# 7CUN_RGB_V0_0_1.net
KiCad netlist of a schematic drawn in Altium Designer
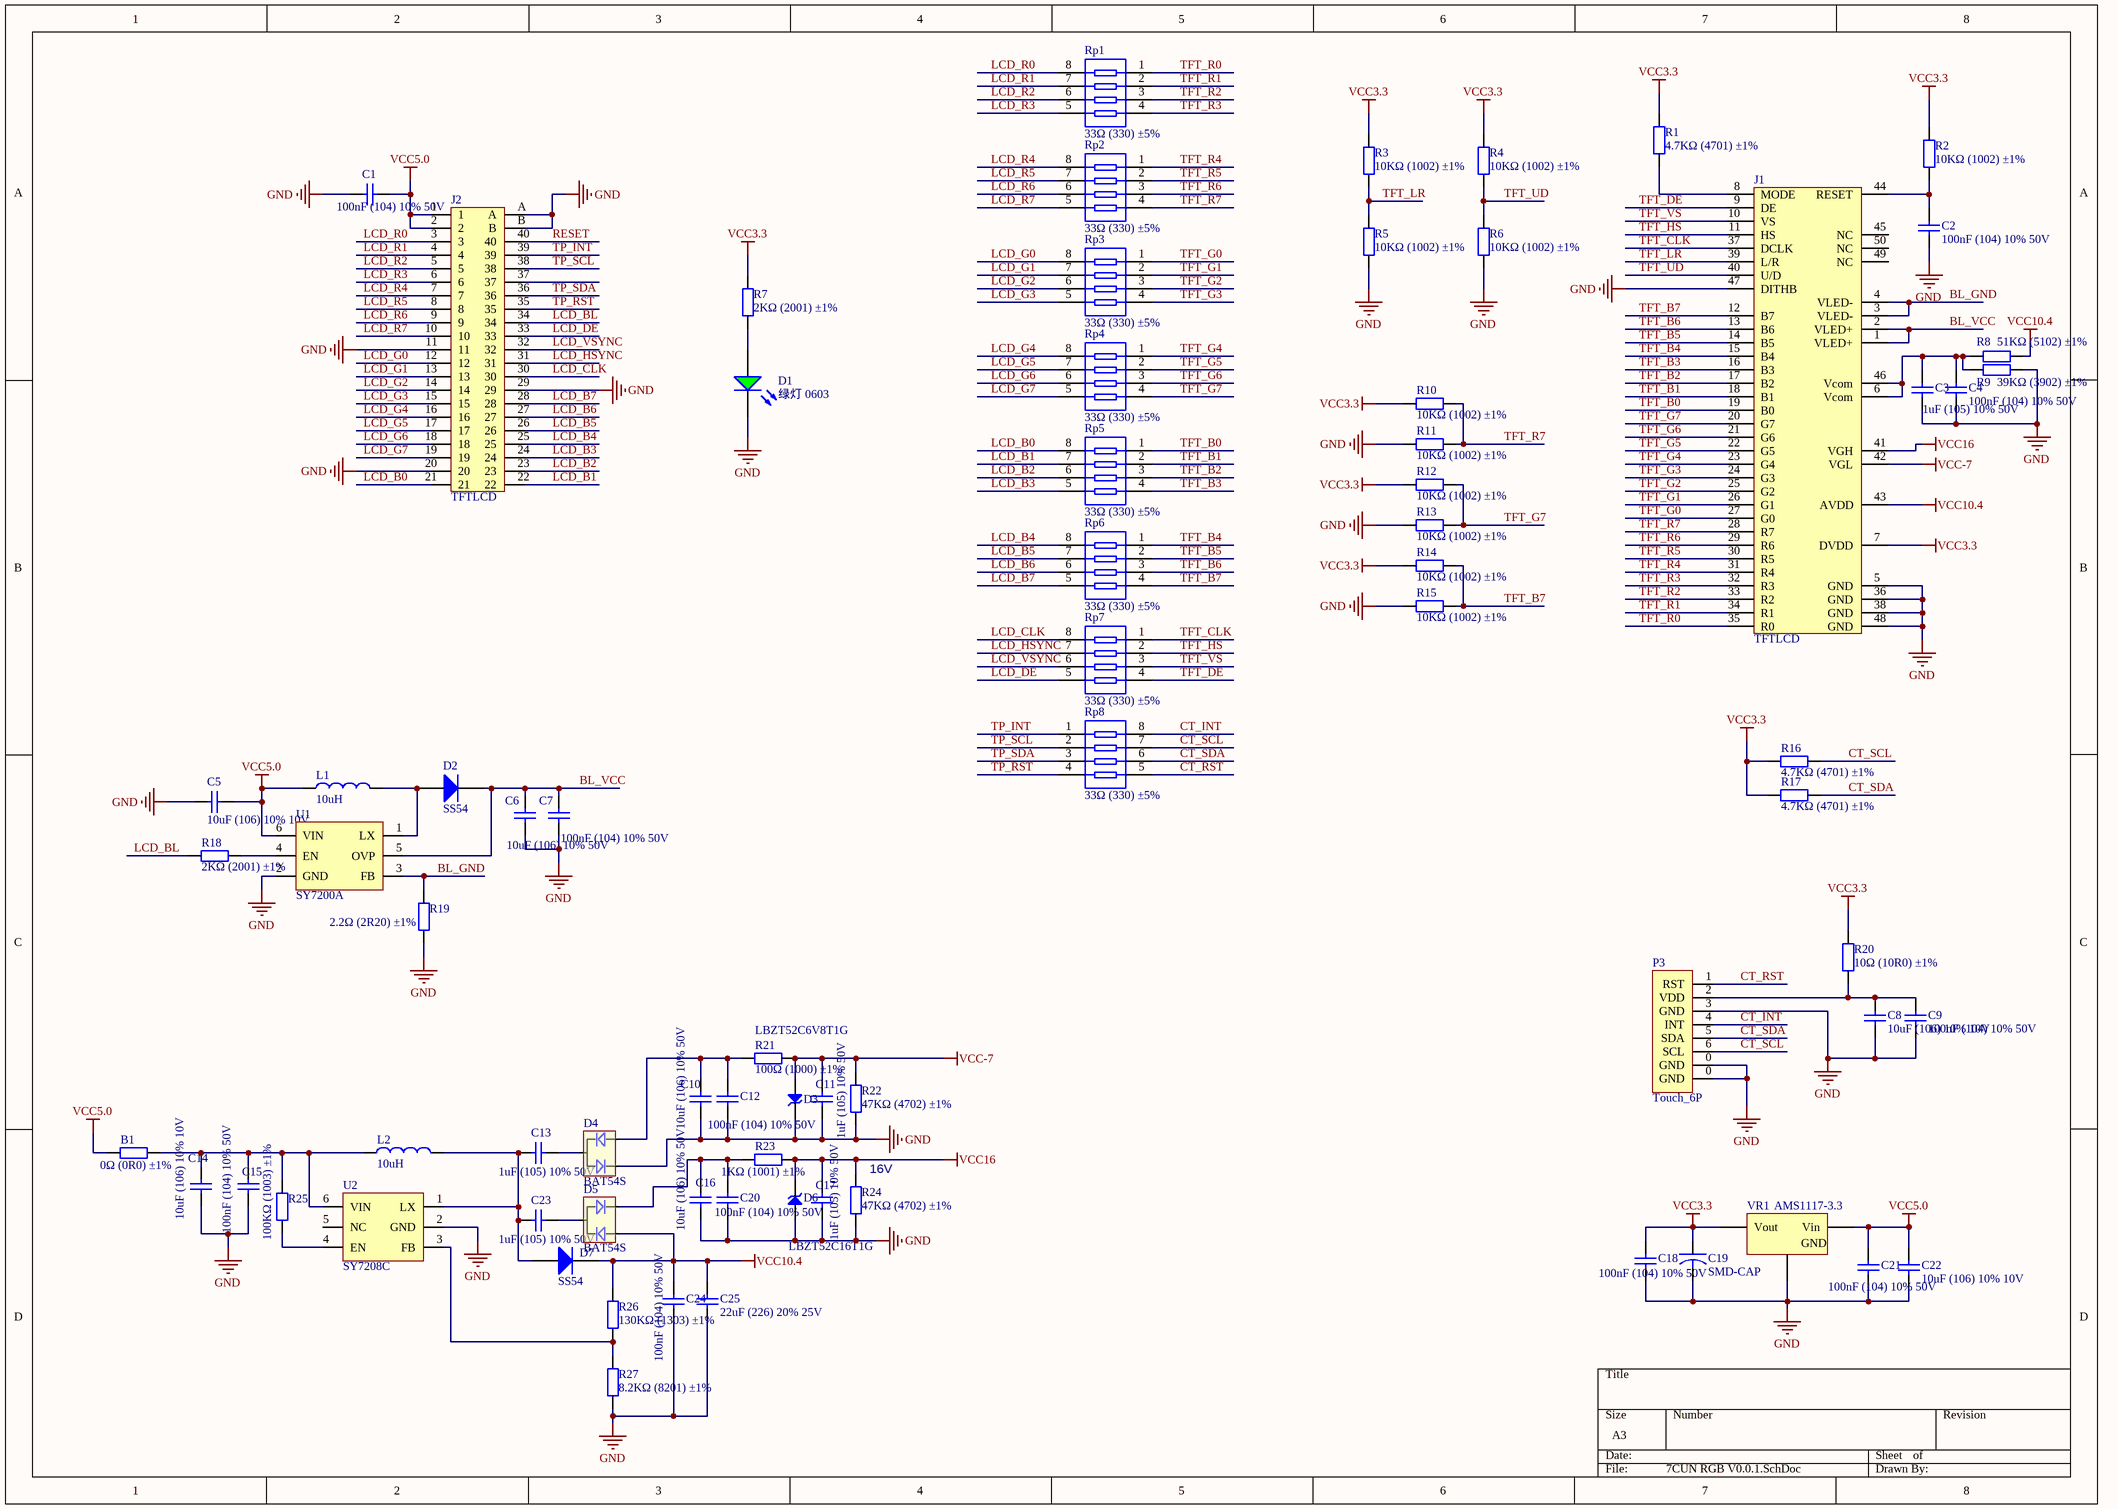
[diagram p0: 7CUN RGB V0.0.1.SchDoc]

(export (version "E")
  (design (tool "Eeschema 10.0.6"))
  (components
    (comp (ref "B1")
      (value "0Ω (0R0) ±1%")
      (footprint "0603_R")
      (description "贴片电阻")
      (libsource (lib "Miscellaneous Devices LC") (part "0603 0Ω (0R0) 1%"))
    )
    (comp (ref "C1")
      (value "100nF (104) 10% 50V")
      (footprint "0603_C")
      (description "贴片电容")
      (libsource (lib "Miscellaneous Devices LC") (part "0603 100nF (104) 10% 50V"))
    )
    (comp (ref "C2")
      (value "100nF (104) 10% 50V")
      (footprint "0603_C")
      (description "贴片电容")
      (libsource (lib "Miscellaneous Devices LC") (part "0603 100nF (104) 10% 50V"))
    )
    (comp (ref "C3")
      (value "1uF (105) 10% 50V")
      (footprint "0603_C")
      (description "贴片电容")
      (libsource (lib "Miscellaneous Devices LC") (part "0603 1uF (105) 10% 50V"))
    )
    (comp (ref "C4")
      (value "100nF (104) 10% 50V")
      (footprint "0603_C")
      (description "贴片电容")
      (libsource (lib "Miscellaneous Devices LC") (part "0603 100nF (104) 10% 50V"))
    )
    (comp (ref "C5")
      (value "10uF (106) 10% 10V")
      (footprint "0603_C")
      (description "贴片电容")
      (libsource (lib "Miscellaneous Devices LC") (part "0603 10uF (106) 10% 10V"))
    )
    (comp (ref "C6")
      (value "10uF (106) 10% 50V")
      (footprint "1206_C")
      (description "贴片电容")
      (libsource (lib "Miscellaneous Devices LC") (part "1206 10uF (106) 10% 50V"))
    )
    (comp (ref "C7")
      (value "100nF (104) 10% 50V")
      (footprint "0603_C")
      (description "贴片电容")
      (libsource (lib "Miscellaneous Devices LC") (part "0603 100nF (104) 10% 50V"))
    )
    (comp (ref "C8")
      (value "10uF (106) 10% 10V")
      (footprint "0603_C")
      (description "贴片电容")
      (libsource (lib "Miscellaneous Devices LC") (part "0603 10uF (106) 10% 10V"))
    )
    (comp (ref "C9")
      (value "100nF (104) 10% 50V")
      (footprint "0603_C")
      (description "贴片电容")
      (libsource (lib "Miscellaneous Devices LC") (part "0603 100nF (104) 10% 50V"))
    )
    (comp (ref "C10")
      (value "10uF (106) 10% 50V")
      (footprint "1206_C")
      (description "贴片电容")
      (libsource (lib "Miscellaneous Devices LC") (part "1206 10uF (106) 10% 50V"))
    )
    (comp (ref "C11")
      (value "1uF (105) 10% 50V")
      (footprint "0603_C")
      (description "贴片电容")
      (libsource (lib "Miscellaneous Devices LC") (part "0603 1uF (105) 10% 50V"))
    )
    (comp (ref "C12")
      (value "100nF (104) 10% 50V")
      (footprint "0603_C")
      (description "贴片电容")
      (libsource (lib "Miscellaneous Devices LC") (part "0603 100nF (104) 10% 50V"))
    )
    (comp (ref "C13")
      (value "1uF (105) 10% 50V")
      (footprint "0603_C")
      (description "贴片电容")
      (libsource (lib "Miscellaneous Devices LC") (part "0603 1uF (105) 10% 50V"))
    )
    (comp (ref "C14")
      (value "10uF (106) 10% 10V")
      (footprint "0603_C")
      (description "贴片电容")
      (libsource (lib "Miscellaneous Devices LC") (part "0603 10uF (106) 10% 10V"))
    )
    (comp (ref "C15")
      (value "100nF (104) 10% 50V")
      (footprint "0603_C")
      (description "贴片电容")
      (libsource (lib "Miscellaneous Devices LC") (part "0603 100nF (104) 10% 50V"))
    )
    (comp (ref "C16")
      (value "10uF (106) 10% 50V")
      (footprint "1206_C")
      (description "贴片电容")
      (libsource (lib "Miscellaneous Devices LC") (part "1206 10uF (106) 10% 50V"))
    )
    (comp (ref "C17")
      (value "1uF (105) 10% 50V")
      (footprint "0603_C")
      (description "贴片电容")
      (libsource (lib "Miscellaneous Devices LC") (part "0603 1uF (105) 10% 50V"))
    )
    (comp (ref "C18")
      (value "100nF (104) 10% 50V")
      (footprint "0603_C")
      (description "贴片电容")
      (libsource (lib "Miscellaneous Devices LC") (part "0603 100nF (104) 10% 50V"))
    )
    (comp (ref "C19") (value "SMD-CAP") (footprint "SMD-6.5mm") (libsource (lib "分立器件") (part "SMD-CAP")))
    (comp (ref "C20")
      (value "100nF (104) 10% 50V")
      (footprint "0603_C")
      (description "贴片电容")
      (libsource (lib "Miscellaneous Devices LC") (part "0603 100nF (104) 10% 50V"))
    )
    (comp (ref "C21")
      (value "100nF (104) 10% 50V")
      (footprint "0603_C")
      (description "贴片电容")
      (libsource (lib "Miscellaneous Devices LC") (part "0603 100nF (104) 10% 50V"))
    )
    (comp (ref "C22")
      (value "10uF (106) 10% 10V")
      (footprint "0603_C")
      (description "贴片电容")
      (libsource (lib "Miscellaneous Devices LC") (part "0603 10uF (106) 10% 10V"))
    )
    (comp (ref "C23")
      (value "1uF (105) 10% 50V")
      (footprint "0603_C")
      (description "贴片电容")
      (libsource (lib "Miscellaneous Devices LC") (part "0603 1uF (105) 10% 50V"))
    )
    (comp (ref "C24")
      (value "100nF (104) 10% 50V")
      (footprint "0603_C")
      (description "贴片电容")
      (libsource (lib "Miscellaneous Devices LC") (part "0603 100nF (104) 10% 50V"))
    )
    (comp (ref "C25")
      (value "22uF (226) 20% 25V")
      (footprint "0805_C")
      (description "贴片电容")
      (libsource (lib "Miscellaneous Devices LC") (part "0805 22uF (226) 20% 25V"))
    )
    (comp (ref "D1")
      (value "绿灯 0603")
      (footprint "0603_LED_S1")
      (description "发光二极管")
      (libsource (lib "Miscellaneous Devices LC") (part "0603 绿灯"))
    )
    (comp (ref "D2")
      (value "SS54")
      (footprint "SMA(DO-214AC)_S1")
      (description "二极管")
      (libsource (lib "Miscellaneous Devices LC") (part "SMA(DO-214AC) SS54"))
    )
    (comp (ref "D3")
      (value "LBZT52C6V8T1G")
      (footprint "DIODE_ZMMx")
      (description "ZMM3V6")
      (libsource (lib "ATK-7016&7084 7寸RGB屏模块封装库") (part "ZMM3V6"))
    )
    (comp (ref "D4")
      (value "BAT54S")
      (footprint "SOT-23")
      (description "双肖特基二极管")
      (libsource (lib "") (part "BAT54S_1"))
    )
    (comp (ref "D5")
      (value "BAT54S")
      (footprint "SOT-23")
      (description "双肖特基二极管")
      (libsource (lib "ATK-7016&7084 7寸RGB屏模块封装库") (part "BAT54S"))
    )
    (comp (ref "D6")
      (value "LBZT52C16T1G")
      (footprint "DIODE_ZMMx")
      (description "ZMM3V6")
      (libsource (lib "ATK-7016&7084 7寸RGB屏模块封装库") (part "ZMM3V6"))
    )
    (comp (ref "D7")
      (value "SS54")
      (footprint "SMA(DO-214AC)_S1")
      (description "二极管")
      (libsource (lib "Miscellaneous Devices LC") (part "SMA(DO-214AC) SS54"))
    )
    (comp (ref "J1")
      (value "TFTLCD")
      (footprint "TFT3.5-50pin下接")
      (description "7' TFTLCD")
      (libsource (lib "ATK-7016&7084 7寸RGB屏模块封装库") (part "AT070TN92"))
    )
    (comp (ref "J2")
      (value "TFTLCD")
      (footprint "FPC-40-0.5MM")
      (description "FPC-40P-0.5mm")
      (libsource (lib "ATK-7016&7084 7寸RGB屏模块封装库") (part "FPC-40"))
    )
    (comp (ref "L1") (value "10uH") (footprint "SOP_5020") (libsource (lib "分立器件") (part "L-SOP(5020)")))
    (comp (ref "L2") (value "10uH") (footprint "SOP_5020") (libsource (lib "分立器件") (part "L-SOP(5020)")))
    (comp (ref "P3") (value "Touch_6P") (footprint "Touch_6P") (libsource (lib "接插件") (part "Touch_6P")))
    (comp (ref "R1")
      (value "4.7KΩ (4701) ±1%")
      (footprint "0603_R")
      (description "贴片电阻")
      (libsource (lib "") (part "0603 4.7KΩ (4701) 1%_1"))
    )
    (comp (ref "R2")
      (value "10KΩ (1002) ±1%")
      (footprint "0603_R")
      (description "贴片电阻")
      (libsource (lib "") (part "0603 10KΩ (1002) 1%_1"))
    )
    (comp (ref "R3")
      (value "10KΩ (1002) ±1%")
      (footprint "0603_R")
      (description "贴片电阻")
      (libsource (lib "") (part "0603 10KΩ (1002) 1%_1"))
    )
    (comp (ref "R4")
      (value "10KΩ (1002) ±1%")
      (footprint "0603_R")
      (description "贴片电阻")
      (libsource (lib "") (part "0603 10KΩ (1002) 1%_1"))
    )
    (comp (ref "R5")
      (value "10KΩ (1002) ±1%")
      (footprint "0603_R")
      (description "贴片电阻")
      (libsource (lib "") (part "0603 10KΩ (1002) 1%_1"))
    )
    (comp (ref "R6")
      (value "10KΩ (1002) ±1%")
      (footprint "0603_R")
      (description "贴片电阻")
      (libsource (lib "") (part "0603 10KΩ (1002) 1%_1"))
    )
    (comp (ref "R7")
      (value "2KΩ (2001) ±1%")
      (footprint "0603_R")
      (description "贴片电阻")
      (libsource (lib "") (part "0603 2KΩ (2001) 1%_1"))
    )
    (comp (ref "R8")
      (value "51KΩ (5102) ±1%")
      (footprint "0603_R")
      (description "贴片电阻")
      (libsource (lib "Miscellaneous Devices LC") (part "0603 51KΩ (5102) 1%"))
    )
    (comp (ref "R9")
      (value "39KΩ (3902) ±1%")
      (footprint "0603_R")
      (description "贴片电阻")
      (libsource (lib "Miscellaneous Devices LC") (part "0603 39KΩ (3902) 1%"))
    )
    (comp (ref "R10")
      (value "10KΩ (1002) ±1%")
      (footprint "0603_R")
      (description "贴片电阻")
      (libsource (lib "Miscellaneous Devices LC") (part "0603 10KΩ (1002) 1%"))
    )
    (comp (ref "R11")
      (value "10KΩ (1002) ±1%")
      (footprint "0603_R")
      (description "贴片电阻")
      (libsource (lib "Miscellaneous Devices LC") (part "0603 10KΩ (1002) 1%"))
    )
    (comp (ref "R12")
      (value "10KΩ (1002) ±1%")
      (footprint "0603_R")
      (description "贴片电阻")
      (libsource (lib "Miscellaneous Devices LC") (part "0603 10KΩ (1002) 1%"))
    )
    (comp (ref "R13")
      (value "10KΩ (1002) ±1%")
      (footprint "0603_R")
      (description "贴片电阻")
      (libsource (lib "Miscellaneous Devices LC") (part "0603 10KΩ (1002) 1%"))
    )
    (comp (ref "R14")
      (value "10KΩ (1002) ±1%")
      (footprint "0603_R")
      (description "贴片电阻")
      (libsource (lib "Miscellaneous Devices LC") (part "0603 10KΩ (1002) 1%"))
    )
    (comp (ref "R15")
      (value "10KΩ (1002) ±1%")
      (footprint "0603_R")
      (description "贴片电阻")
      (libsource (lib "Miscellaneous Devices LC") (part "0603 10KΩ (1002) 1%"))
    )
    (comp (ref "R16")
      (value "4.7KΩ (4701) ±1%")
      (footprint "0603_R")
      (description "贴片电阻")
      (libsource (lib "Miscellaneous Devices LC") (part "0603 4.7KΩ (4701) 1%"))
    )
    (comp (ref "R17")
      (value "4.7KΩ (4701) ±1%")
      (footprint "0603_R")
      (description "贴片电阻")
      (libsource (lib "Miscellaneous Devices LC") (part "0603 4.7KΩ (4701) 1%"))
    )
    (comp (ref "R18")
      (value "2KΩ (2001) ±1%")
      (footprint "0603_R")
      (description "贴片电阻")
      (libsource (lib "Miscellaneous Devices LC") (part "0603 2KΩ (2001) 1%"))
    )
    (comp (ref "R19")
      (value "2.2Ω (2R20) ±1%")
      (footprint "0603_R")
      (description "贴片电阻")
      (libsource (lib "Miscellaneous Devices LC") (part "0603 2.2Ω (2R20) 1%"))
    )
    (comp (ref "R20")
      (value "10Ω (10R0) ±1%")
      (footprint "0603_R")
      (description "贴片电阻")
      (libsource (lib "Miscellaneous Devices LC") (part "0603 10Ω (10R0) 1%"))
    )
    (comp (ref "R21")
      (value "100Ω (1000) ±1%")
      (footprint "0603_R")
      (description "贴片电阻")
      (libsource (lib "Miscellaneous Devices LC") (part "0603 100Ω (1000) 1%"))
    )
    (comp (ref "R22")
      (value "47KΩ (4702) ±1%")
      (footprint "0603_R")
      (description "贴片电阻")
      (libsource (lib "Miscellaneous Devices LC") (part "0603 47KΩ (4702) 1%"))
    )
    (comp (ref "R23")
      (value "1KΩ (1001) ±1%")
      (footprint "0603_R")
      (description "贴片电阻")
      (libsource (lib "Miscellaneous Devices LC") (part "0603 1KΩ (1001) 1%"))
    )
    (comp (ref "R24")
      (value "47KΩ (4702) ±1%")
      (footprint "0603_R")
      (description "贴片电阻")
      (libsource (lib "Miscellaneous Devices LC") (part "0603 47KΩ (4702) 1%"))
    )
    (comp (ref "R25")
      (value "100KΩ (1003) ±1%")
      (footprint "0603_R")
      (description "贴片电阻")
      (libsource (lib "Miscellaneous Devices LC") (part "0603 100KΩ (1003) 1%"))
    )
    (comp (ref "R26")
      (value "130KΩ (1303) ±1%")
      (footprint "0603_R")
      (description "贴片电阻")
      (libsource (lib "Miscellaneous Devices LC") (part "0603 130KΩ (1303) 1%"))
    )
    (comp (ref "R27")
      (value "8.2KΩ (8201) ±1%")
      (footprint "0603_R")
      (description "贴片电阻")
      (libsource (lib "Miscellaneous Devices LC") (part "0603 8.2KΩ (8201) 1%"))
    )
    (comp (ref "Rp1")
      (value "33Ω (330) ±5%")
      (footprint "0402_Rx4")
      (description "贴片排阻")
      (libsource (lib "Miscellaneous Devices LC") (part "0402*4 33Ω (330) 5%"))
    )
    (comp (ref "Rp2")
      (value "33Ω (330) ±5%")
      (footprint "0402_Rx4")
      (description "贴片排阻")
      (libsource (lib "Miscellaneous Devices LC") (part "0402*4 33Ω (330) 5%"))
    )
    (comp (ref "Rp3")
      (value "33Ω (330) ±5%")
      (footprint "0402_Rx4")
      (description "贴片排阻")
      (libsource (lib "Miscellaneous Devices LC") (part "0402*4 33Ω (330) 5%"))
    )
    (comp (ref "Rp4")
      (value "33Ω (330) ±5%")
      (footprint "0402_Rx4")
      (description "贴片排阻")
      (libsource (lib "Miscellaneous Devices LC") (part "0402*4 33Ω (330) 5%"))
    )
    (comp (ref "Rp5")
      (value "33Ω (330) ±5%")
      (footprint "0402_Rx4")
      (description "贴片排阻")
      (libsource (lib "Miscellaneous Devices LC") (part "0402*4 33Ω (330) 5%"))
    )
    (comp (ref "Rp6")
      (value "33Ω (330) ±5%")
      (footprint "0402_Rx4")
      (description "贴片排阻")
      (libsource (lib "Miscellaneous Devices LC") (part "0402*4 33Ω (330) 5%"))
    )
    (comp (ref "Rp7")
      (value "33Ω (330) ±5%")
      (footprint "0402_Rx4")
      (description "贴片排阻")
      (libsource (lib "Miscellaneous Devices LC") (part "0402*4 33Ω (330) 5%"))
    )
    (comp (ref "Rp8")
      (value "33Ω (330) ±5%")
      (footprint "0402_Rx4")
      (description "贴片排阻")
      (libsource (lib "Miscellaneous Devices LC") (part "0402*4 33Ω (330) 5%"))
    )
    (comp (ref "U1") (value "SY7200A") (footprint "SOT23-6") (libsource (lib "集成块") (part "SY7200A")))
    (comp (ref "U2") (value "SY7208C") (footprint "SOT23-6") (libsource (lib "集成块") (part "SY7208C")))
    (comp (ref "VR1")
      (value "AMS1117-3.3")
      (footprint "SOT-223")
      (description "低压差线性稳压(LDO)")
      (libsource (lib "Miscellaneous Devices LC") (part "SOT-223 AMS1117-3.3"))
    )
  )
  (nets
    (net (code "1") (name "/BL_GND") (class "Default")
      (node (ref "J1") (pin "3") (pinfunction "VLED-_3") (pintype "passive"))
      (node (ref "J1") (pin "4") (pinfunction "VLED-_4") (pintype "passive"))
      (node (ref "R19") (pin "2") (pinfunction "2_2") (pintype "passive"))
      (node (ref "U1") (pin "3") (pinfunction "FB_3") (pintype "passive"))
    )
    (net (code "2") (name "/BL_VCC") (class "Default")
      (node (ref "C6") (pin "2") (pinfunction "2_2") (pintype "passive"))
      (node (ref "C7") (pin "2") (pinfunction "2_2") (pintype "passive"))
      (node (ref "D2") (pin "2") (pinfunction "K_2") (pintype "passive"))
      (node (ref "J1") (pin "1") (pinfunction "VLED+_1") (pintype "passive"))
      (node (ref "J1") (pin "2") (pinfunction "VLED+_2") (pintype "passive"))
      (node (ref "U1") (pin "5") (pinfunction "OVP_5") (pintype "passive"))
    )
    (net (code "3") (name "/CT_INT") (class "Default")
      (node (ref "P3") (pin "4") (pinfunction "INT_4") (pintype "passive"))
      (node (ref "Rp8") (pin "8") (pinfunction "8_8") (pintype "passive"))
    )
    (net (code "4") (name "/CT_RST") (class "Default")
      (node (ref "P3") (pin "1") (pinfunction "RST_1") (pintype "passive"))
      (node (ref "Rp8") (pin "5") (pinfunction "5_5") (pintype "passive"))
    )
    (net (code "5") (name "/CT_SCL") (class "Default")
      (node (ref "P3") (pin "6") (pinfunction "SCL_6") (pintype "passive"))
      (node (ref "R16") (pin "2") (pinfunction "2_2") (pintype "passive"))
      (node (ref "Rp8") (pin "7") (pinfunction "7_7") (pintype "passive"))
    )
    (net (code "6") (name "/CT_SDA") (class "Default")
      (node (ref "P3") (pin "5") (pinfunction "SDA_5") (pintype "passive"))
      (node (ref "R17") (pin "2") (pinfunction "2_2") (pintype "passive"))
      (node (ref "Rp8") (pin "6") (pinfunction "6_6") (pintype "passive"))
    )
    (net (code "7") (name "/LCD_B0") (class "Default")
      (node (ref "J2") (pin "21") (pinfunction "21_21") (pintype "passive"))
      (node (ref "Rp5") (pin "8") (pinfunction "8_8") (pintype "passive"))
    )
    (net (code "8") (name "/LCD_B1") (class "Default")
      (node (ref "J2") (pin "22") (pinfunction "22_22") (pintype "passive"))
      (node (ref "Rp5") (pin "7") (pinfunction "7_7") (pintype "passive"))
    )
    (net (code "9") (name "/LCD_B2") (class "Default")
      (node (ref "J2") (pin "23") (pinfunction "23_23") (pintype "passive"))
      (node (ref "Rp5") (pin "6") (pinfunction "6_6") (pintype "passive"))
    )
    (net (code "10") (name "/LCD_B3") (class "Default")
      (node (ref "J2") (pin "24") (pinfunction "24_24") (pintype "passive"))
      (node (ref "Rp5") (pin "5") (pinfunction "5_5") (pintype "passive"))
    )
    (net (code "11") (name "/LCD_B4") (class "Default")
      (node (ref "J2") (pin "25") (pinfunction "25_25") (pintype "passive"))
      (node (ref "Rp6") (pin "8") (pinfunction "8_8") (pintype "passive"))
    )
    (net (code "12") (name "/LCD_B5") (class "Default")
      (node (ref "J2") (pin "26") (pinfunction "26_26") (pintype "passive"))
      (node (ref "Rp6") (pin "7") (pinfunction "7_7") (pintype "passive"))
    )
    (net (code "13") (name "/LCD_B6") (class "Default")
      (node (ref "J2") (pin "27") (pinfunction "27_27") (pintype "passive"))
      (node (ref "Rp6") (pin "6") (pinfunction "6_6") (pintype "passive"))
    )
    (net (code "14") (name "/LCD_B7") (class "Default")
      (node (ref "J2") (pin "28") (pinfunction "28_28") (pintype "passive"))
      (node (ref "Rp6") (pin "5") (pinfunction "5_5") (pintype "passive"))
    )
    (net (code "15") (name "/LCD_BL") (class "Default")
      (node (ref "J2") (pin "34") (pinfunction "34_34") (pintype "passive"))
      (node (ref "R18") (pin "1") (pinfunction "1_1") (pintype "passive"))
    )
    (net (code "16") (name "/LCD_CLK") (class "Default")
      (node (ref "J2") (pin "30") (pinfunction "30_30") (pintype "passive"))
      (node (ref "Rp7") (pin "8") (pinfunction "8_8") (pintype "passive"))
    )
    (net (code "17") (name "/LCD_DE") (class "Default")
      (node (ref "J2") (pin "33") (pinfunction "33_33") (pintype "passive"))
      (node (ref "Rp7") (pin "5") (pinfunction "5_5") (pintype "passive"))
    )
    (net (code "18") (name "/LCD_G0") (class "Default")
      (node (ref "J2") (pin "12") (pinfunction "12_12") (pintype "passive"))
      (node (ref "Rp3") (pin "8") (pinfunction "8_8") (pintype "passive"))
    )
    (net (code "19") (name "/LCD_G1") (class "Default")
      (node (ref "J2") (pin "13") (pinfunction "13_13") (pintype "passive"))
      (node (ref "Rp3") (pin "7") (pinfunction "7_7") (pintype "passive"))
    )
    (net (code "20") (name "/LCD_G2") (class "Default")
      (node (ref "J2") (pin "14") (pinfunction "14_14") (pintype "passive"))
      (node (ref "Rp3") (pin "6") (pinfunction "6_6") (pintype "passive"))
    )
    (net (code "21") (name "/LCD_G3") (class "Default")
      (node (ref "J2") (pin "15") (pinfunction "15_15") (pintype "passive"))
      (node (ref "Rp3") (pin "5") (pinfunction "5_5") (pintype "passive"))
    )
    (net (code "22") (name "/LCD_G4") (class "Default")
      (node (ref "J2") (pin "16") (pinfunction "16_16") (pintype "passive"))
      (node (ref "Rp4") (pin "8") (pinfunction "8_8") (pintype "passive"))
    )
    (net (code "23") (name "/LCD_G5") (class "Default")
      (node (ref "J2") (pin "17") (pinfunction "17_17") (pintype "passive"))
      (node (ref "Rp4") (pin "7") (pinfunction "7_7") (pintype "passive"))
    )
    (net (code "24") (name "/LCD_G6") (class "Default")
      (node (ref "J2") (pin "18") (pinfunction "18_18") (pintype "passive"))
      (node (ref "Rp4") (pin "6") (pinfunction "6_6") (pintype "passive"))
    )
    (net (code "25") (name "/LCD_G7") (class "Default")
      (node (ref "J2") (pin "19") (pinfunction "19_19") (pintype "passive"))
      (node (ref "Rp4") (pin "5") (pinfunction "5_5") (pintype "passive"))
    )
    (net (code "26") (name "/LCD_HSYNC") (class "Default")
      (node (ref "J2") (pin "31") (pinfunction "31_31") (pintype "passive"))
      (node (ref "Rp7") (pin "7") (pinfunction "7_7") (pintype "passive"))
    )
    (net (code "27") (name "/LCD_R0") (class "Default")
      (node (ref "J2") (pin "3") (pinfunction "3_3") (pintype "passive"))
      (node (ref "Rp1") (pin "8") (pinfunction "8_8") (pintype "passive"))
    )
    (net (code "28") (name "/LCD_R1") (class "Default")
      (node (ref "J2") (pin "4") (pinfunction "4_4") (pintype "passive"))
      (node (ref "Rp1") (pin "7") (pinfunction "7_7") (pintype "passive"))
    )
    (net (code "29") (name "/LCD_R2") (class "Default")
      (node (ref "J2") (pin "5") (pinfunction "5_5") (pintype "passive"))
      (node (ref "Rp1") (pin "6") (pinfunction "6_6") (pintype "passive"))
    )
    (net (code "30") (name "/LCD_R3") (class "Default")
      (node (ref "J2") (pin "6") (pinfunction "6_6") (pintype "passive"))
      (node (ref "Rp1") (pin "5") (pinfunction "5_5") (pintype "passive"))
    )
    (net (code "31") (name "/LCD_R4") (class "Default")
      (node (ref "J2") (pin "7") (pinfunction "7_7") (pintype "passive"))
      (node (ref "Rp2") (pin "8") (pinfunction "8_8") (pintype "passive"))
    )
    (net (code "32") (name "/LCD_R5") (class "Default")
      (node (ref "J2") (pin "8") (pinfunction "8_8") (pintype "passive"))
      (node (ref "Rp2") (pin "7") (pinfunction "7_7") (pintype "passive"))
    )
    (net (code "33") (name "/LCD_R6") (class "Default")
      (node (ref "J2") (pin "9") (pinfunction "9_9") (pintype "passive"))
      (node (ref "Rp2") (pin "6") (pinfunction "6_6") (pintype "passive"))
    )
    (net (code "34") (name "/LCD_R7") (class "Default")
      (node (ref "J2") (pin "10") (pinfunction "10_10") (pintype "passive"))
      (node (ref "Rp2") (pin "5") (pinfunction "5_5") (pintype "passive"))
    )
    (net (code "35") (name "/LCD_VSYNC") (class "Default")
      (node (ref "J2") (pin "32") (pinfunction "32_32") (pintype "passive"))
      (node (ref "Rp7") (pin "6") (pinfunction "6_6") (pintype "passive"))
    )
    (net (code "36") (name "/RESET") (class "Default")
      (node (ref "J2") (pin "40") (pinfunction "40_40") (pintype "passive"))
    )
    (net (code "37") (name "/TFT_B0") (class "Default")
      (node (ref "J1") (pin "19") (pinfunction "B0_19") (pintype "passive"))
      (node (ref "Rp5") (pin "1") (pinfunction "1_1") (pintype "passive"))
    )
    (net (code "38") (name "/TFT_B1") (class "Default")
      (node (ref "J1") (pin "18") (pinfunction "B1_18") (pintype "passive"))
      (node (ref "Rp5") (pin "2") (pinfunction "2_2") (pintype "passive"))
    )
    (net (code "39") (name "/TFT_B2") (class "Default")
      (node (ref "J1") (pin "17") (pinfunction "B2_17") (pintype "passive"))
      (node (ref "Rp5") (pin "3") (pinfunction "3_3") (pintype "passive"))
    )
    (net (code "40") (name "/TFT_B3") (class "Default")
      (node (ref "J1") (pin "16") (pinfunction "B3_16") (pintype "passive"))
      (node (ref "Rp5") (pin "4") (pinfunction "4_4") (pintype "passive"))
    )
    (net (code "41") (name "/TFT_B4") (class "Default")
      (node (ref "J1") (pin "15") (pinfunction "B4_15") (pintype "passive"))
      (node (ref "Rp6") (pin "1") (pinfunction "1_1") (pintype "passive"))
    )
    (net (code "42") (name "/TFT_B5") (class "Default")
      (node (ref "J1") (pin "14") (pinfunction "B5_14") (pintype "passive"))
      (node (ref "Rp6") (pin "2") (pinfunction "2_2") (pintype "passive"))
    )
    (net (code "43") (name "/TFT_B6") (class "Default")
      (node (ref "J1") (pin "13") (pinfunction "B6_13") (pintype "passive"))
      (node (ref "Rp6") (pin "3") (pinfunction "3_3") (pintype "passive"))
    )
    (net (code "44") (name "/TFT_B7") (class "Default")
      (node (ref "J1") (pin "12") (pinfunction "B7_12") (pintype "passive"))
      (node (ref "R14") (pin "1") (pinfunction "1_1") (pintype "passive"))
      (node (ref "R15") (pin "1") (pinfunction "1_1") (pintype "passive"))
      (node (ref "Rp6") (pin "4") (pinfunction "4_4") (pintype "passive"))
    )
    (net (code "45") (name "/TFT_CLK") (class "Default")
      (node (ref "J1") (pin "37") (pinfunction "DCLK_37") (pintype "passive"))
      (node (ref "Rp7") (pin "1") (pinfunction "1_1") (pintype "passive"))
    )
    (net (code "46") (name "/TFT_DE") (class "Default")
      (node (ref "J1") (pin "9") (pinfunction "DE_9") (pintype "passive"))
      (node (ref "Rp7") (pin "4") (pinfunction "4_4") (pintype "passive"))
    )
    (net (code "47") (name "/TFT_G0") (class "Default")
      (node (ref "J1") (pin "27") (pinfunction "G0_27") (pintype "passive"))
      (node (ref "Rp3") (pin "1") (pinfunction "1_1") (pintype "passive"))
    )
    (net (code "48") (name "/TFT_G1") (class "Default")
      (node (ref "J1") (pin "26") (pinfunction "G1_26") (pintype "passive"))
      (node (ref "Rp3") (pin "2") (pinfunction "2_2") (pintype "passive"))
    )
    (net (code "49") (name "/TFT_G2") (class "Default")
      (node (ref "J1") (pin "25") (pinfunction "G2_25") (pintype "passive"))
      (node (ref "Rp3") (pin "3") (pinfunction "3_3") (pintype "passive"))
    )
    (net (code "50") (name "/TFT_G3") (class "Default")
      (node (ref "J1") (pin "24") (pinfunction "G3_24") (pintype "passive"))
      (node (ref "Rp3") (pin "4") (pinfunction "4_4") (pintype "passive"))
    )
    (net (code "51") (name "/TFT_G4") (class "Default")
      (node (ref "J1") (pin "23") (pinfunction "G4_23") (pintype "passive"))
      (node (ref "Rp4") (pin "1") (pinfunction "1_1") (pintype "passive"))
    )
    (net (code "52") (name "/TFT_G5") (class "Default")
      (node (ref "J1") (pin "22") (pinfunction "G5_22") (pintype "passive"))
      (node (ref "Rp4") (pin "2") (pinfunction "2_2") (pintype "passive"))
    )
    (net (code "53") (name "/TFT_G6") (class "Default")
      (node (ref "J1") (pin "21") (pinfunction "G6_21") (pintype "passive"))
      (node (ref "Rp4") (pin "3") (pinfunction "3_3") (pintype "passive"))
    )
    (net (code "54") (name "/TFT_G7") (class "Default")
      (node (ref "J1") (pin "20") (pinfunction "G7_20") (pintype "passive"))
      (node (ref "R12") (pin "1") (pinfunction "1_1") (pintype "passive"))
      (node (ref "R13") (pin "1") (pinfunction "1_1") (pintype "passive"))
      (node (ref "Rp4") (pin "4") (pinfunction "4_4") (pintype "passive"))
    )
    (net (code "55") (name "/TFT_HS") (class "Default")
      (node (ref "J1") (pin "11") (pinfunction "HS_11") (pintype "passive"))
      (node (ref "Rp7") (pin "2") (pinfunction "2_2") (pintype "passive"))
    )
    (net (code "56") (name "/TFT_LR") (class "Default")
      (node (ref "J1") (pin "39") (pinfunction "L/R_39") (pintype "passive"))
      (node (ref "R3") (pin "1") (pinfunction "1_1") (pintype "passive"))
      (node (ref "R5") (pin "2") (pinfunction "2_2") (pintype "passive"))
    )
    (net (code "57") (name "/TFT_R0") (class "Default")
      (node (ref "J1") (pin "35") (pinfunction "R0_35") (pintype "passive"))
      (node (ref "Rp1") (pin "1") (pinfunction "1_1") (pintype "passive"))
    )
    (net (code "58") (name "/TFT_R1") (class "Default")
      (node (ref "J1") (pin "34") (pinfunction "R1_34") (pintype "passive"))
      (node (ref "Rp1") (pin "2") (pinfunction "2_2") (pintype "passive"))
    )
    (net (code "59") (name "/TFT_R2") (class "Default")
      (node (ref "J1") (pin "33") (pinfunction "R2_33") (pintype "passive"))
      (node (ref "Rp1") (pin "3") (pinfunction "3_3") (pintype "passive"))
    )
    (net (code "60") (name "/TFT_R3") (class "Default")
      (node (ref "J1") (pin "32") (pinfunction "R3_32") (pintype "passive"))
      (node (ref "Rp1") (pin "4") (pinfunction "4_4") (pintype "passive"))
    )
    (net (code "61") (name "/TFT_R4") (class "Default")
      (node (ref "J1") (pin "31") (pinfunction "R4_31") (pintype "passive"))
      (node (ref "Rp2") (pin "1") (pinfunction "1_1") (pintype "passive"))
    )
    (net (code "62") (name "/TFT_R5") (class "Default")
      (node (ref "J1") (pin "30") (pinfunction "R5_30") (pintype "passive"))
      (node (ref "Rp2") (pin "2") (pinfunction "2_2") (pintype "passive"))
    )
    (net (code "63") (name "/TFT_R6") (class "Default")
      (node (ref "J1") (pin "29") (pinfunction "R6_29") (pintype "passive"))
      (node (ref "Rp2") (pin "3") (pinfunction "3_3") (pintype "passive"))
    )
    (net (code "64") (name "/TFT_R7") (class "Default")
      (node (ref "J1") (pin "28") (pinfunction "R7_28") (pintype "passive"))
      (node (ref "R10") (pin "1") (pinfunction "1_1") (pintype "passive"))
      (node (ref "R11") (pin "1") (pinfunction "1_1") (pintype "passive"))
      (node (ref "Rp2") (pin "4") (pinfunction "4_4") (pintype "passive"))
    )
    (net (code "65") (name "/TFT_UD") (class "Default")
      (node (ref "J1") (pin "40") (pinfunction "U/D_40") (pintype "passive"))
      (node (ref "R4") (pin "1") (pinfunction "1_1") (pintype "passive"))
      (node (ref "R6") (pin "2") (pinfunction "2_2") (pintype "passive"))
    )
    (net (code "66") (name "/TFT_VS") (class "Default")
      (node (ref "J1") (pin "10") (pinfunction "VS_10") (pintype "passive"))
      (node (ref "Rp7") (pin "3") (pinfunction "3_3") (pintype "passive"))
    )
    (net (code "67") (name "/TP_INT") (class "Default")
      (node (ref "J2") (pin "39") (pinfunction "39_39") (pintype "passive"))
      (node (ref "Rp8") (pin "1") (pinfunction "1_1") (pintype "passive"))
    )
    (net (code "68") (name "/TP_RST") (class "Default")
      (node (ref "J2") (pin "35") (pinfunction "35_35") (pintype "passive"))
      (node (ref "Rp8") (pin "4") (pinfunction "4_4") (pintype "passive"))
    )
    (net (code "69") (name "/TP_SCL") (class "Default")
      (node (ref "J2") (pin "38") (pinfunction "38_38") (pintype "passive"))
      (node (ref "Rp8") (pin "2") (pinfunction "2_2") (pintype "passive"))
    )
    (net (code "70") (name "/TP_SDA") (class "Default")
      (node (ref "J2") (pin "36") (pinfunction "36_36") (pintype "passive"))
      (node (ref "Rp8") (pin "3") (pinfunction "3_3") (pintype "passive"))
    )
    (net (code "71") (name "GND") (class "Default")
      (node (ref "C1") (pin "2") (pinfunction "2_2") (pintype "passive"))
      (node (ref "C10") (pin "1") (pinfunction "1_1") (pintype "passive"))
      (node (ref "C11") (pin "1") (pinfunction "1_1") (pintype "passive"))
      (node (ref "C12") (pin "1") (pinfunction "1_1") (pintype "passive"))
      (node (ref "C14") (pin "1") (pinfunction "1_1") (pintype "passive"))
      (node (ref "C15") (pin "1") (pinfunction "1_1") (pintype "passive"))
      (node (ref "C16") (pin "1") (pinfunction "1_1") (pintype "passive"))
      (node (ref "C17") (pin "1") (pinfunction "1_1") (pintype "passive"))
      (node (ref "C18") (pin "1") (pinfunction "1_1") (pintype "passive"))
      (node (ref "C19") (pin "2") (pinfunction "2_2") (pintype "passive"))
      (node (ref "C2") (pin "1") (pinfunction "1_1") (pintype "passive"))
      (node (ref "C20") (pin "1") (pinfunction "1_1") (pintype "passive"))
      (node (ref "C21") (pin "1") (pinfunction "1_1") (pintype "passive"))
      (node (ref "C22") (pin "1") (pinfunction "1_1") (pintype "passive"))
      (node (ref "C24") (pin "1") (pinfunction "1_1") (pintype "passive"))
      (node (ref "C25") (pin "1") (pinfunction "1_1") (pintype "passive"))
      (node (ref "C3") (pin "1") (pinfunction "1_1") (pintype "passive"))
      (node (ref "C4") (pin "1") (pinfunction "1_1") (pintype "passive"))
      (node (ref "C5") (pin "2") (pinfunction "2_2") (pintype "passive"))
      (node (ref "C6") (pin "1") (pinfunction "1_1") (pintype "passive"))
      (node (ref "C7") (pin "1") (pinfunction "1_1") (pintype "passive"))
      (node (ref "C8") (pin "1") (pinfunction "1_1") (pintype "passive"))
      (node (ref "C9") (pin "1") (pinfunction "1_1") (pintype "passive"))
      (node (ref "D1") (pin "K") (pinfunction "K_K") (pintype "passive"))
      (node (ref "D3") (pin "2") (pintype "passive"))
      (node (ref "D4") (pin "2") (pintype "passive"))
      (node (ref "D6") (pin "1") (pintype "passive"))
      (node (ref "J1") (pin "36") (pinfunction "GND_36") (pintype "passive"))
      (node (ref "J1") (pin "38") (pinfunction "GND_38") (pintype "passive"))
      (node (ref "J1") (pin "47") (pinfunction "DITHB_47") (pintype "passive"))
      (node (ref "J1") (pin "48") (pinfunction "GND_48") (pintype "passive"))
      (node (ref "J1") (pin "5") (pinfunction "GND_5") (pintype "passive"))
      (node (ref "J2") (pin "11") (pinfunction "11_11") (pintype "passive"))
      (node (ref "J2") (pin "20") (pinfunction "20_20") (pintype "passive"))
      (node (ref "J2") (pin "29") (pinfunction "29_29") (pintype "passive"))
      (node (ref "J2") (pin "A") (pinfunction "A_A") (pintype "passive"))
      (node (ref "J2") (pin "B") (pinfunction "B_B") (pintype "passive"))
      (node (ref "P3") (pin "0") (pinfunction "GND_0") (pintype "passive"))
      (node (ref "P3") (pin "3") (pinfunction "GND_3") (pintype "passive"))
      (node (ref "R11") (pin "2") (pinfunction "2_2") (pintype "passive"))
      (node (ref "R13") (pin "2") (pinfunction "2_2") (pintype "passive"))
      (node (ref "R15") (pin "2") (pinfunction "2_2") (pintype "passive"))
      (node (ref "R19") (pin "1") (pinfunction "1_1") (pintype "passive"))
      (node (ref "R22") (pin "1") (pinfunction "1_1") (pintype "passive"))
      (node (ref "R24") (pin "1") (pinfunction "1_1") (pintype "passive"))
      (node (ref "R27") (pin "1") (pinfunction "1_1") (pintype "passive"))
      (node (ref "R5") (pin "1") (pinfunction "1_1") (pintype "passive"))
      (node (ref "R6") (pin "1") (pinfunction "1_1") (pintype "passive"))
      (node (ref "R9") (pin "2") (pinfunction "2_2") (pintype "passive"))
      (node (ref "U1") (pin "2") (pinfunction "GND_2") (pintype "passive"))
      (node (ref "U2") (pin "2") (pinfunction "GND_2") (pintype "passive"))
      (node (ref "VR1") (pin "1") (pinfunction "GND_1") (pintype "passive"))
    )
    (net (code "72") (name "Net-(C3-Pad2)") (class "Default")
      (node (ref "C3") (pin "2") (pinfunction "2_2") (pintype "passive"))
      (node (ref "C4") (pin "2") (pinfunction "2_2") (pintype "passive"))
      (node (ref "J1") (pin "46") (pinfunction "Vcom_46") (pintype "passive"))
      (node (ref "J1") (pin "6") (pinfunction "Vcom_6") (pintype "passive"))
      (node (ref "R8") (pin "1") (pinfunction "1_1") (pintype "passive"))
      (node (ref "R9") (pin "1") (pinfunction "1_1") (pintype "passive"))
    )
    (net (code "73") (name "Net-(C10-Pad2)") (class "Default")
      (node (ref "C10") (pin "2") (pinfunction "2_2") (pintype "passive"))
      (node (ref "C12") (pin "2") (pinfunction "2_2") (pintype "passive"))
      (node (ref "D4") (pin "1") (pintype "passive"))
      (node (ref "R21") (pin "1") (pinfunction "1_1") (pintype "passive"))
    )
    (net (code "74") (name "Net-(C13-Pad2)") (class "Default")
      (node (ref "C13") (pin "2") (pinfunction "2_2") (pintype "passive"))
      (node (ref "D4") (pin "3") (pintype "passive"))
    )
    (net (code "75") (name "Net-(C16-Pad2)") (class "Default")
      (node (ref "C16") (pin "2") (pinfunction "2_2") (pintype "passive"))
      (node (ref "C20") (pin "2") (pinfunction "2_2") (pintype "passive"))
      (node (ref "D5") (pin "2") (pintype "passive"))
      (node (ref "R23") (pin "1") (pinfunction "1_1") (pintype "passive"))
    )
    (net (code "76") (name "Net-(C23-Pad2)") (class "Default")
      (node (ref "C23") (pin "2") (pinfunction "2_2") (pintype "passive"))
      (node (ref "D5") (pin "3") (pintype "passive"))
    )
    (net (code "77") (name "Net-(D1-PadA)") (class "Default")
      (node (ref "D1") (pin "A") (pinfunction "A_A") (pintype "passive"))
      (node (ref "R7") (pin "1") (pinfunction "1_1") (pintype "passive"))
    )
    (net (code "78") (name "Net-(D2-A)") (class "Default")
      (node (ref "D2") (pin "1") (pinfunction "A_1") (pintype "passive"))
      (node (ref "L1") (pin "2") (pinfunction "2_2") (pintype "passive"))
      (node (ref "U1") (pin "1") (pinfunction "LX_1") (pintype "passive"))
    )
    (net (code "79") (name "Net-(D7-A)") (class "Default")
      (node (ref "C13") (pin "1") (pinfunction "1_1") (pintype "passive"))
      (node (ref "C23") (pin "1") (pinfunction "1_1") (pintype "passive"))
      (node (ref "D7") (pin "1") (pinfunction "A_1") (pintype "passive"))
      (node (ref "L2") (pin "2") (pinfunction "2_2") (pintype "passive"))
      (node (ref "U2") (pin "1") (pinfunction "LX_1") (pintype "passive"))
    )
    (net (code "80") (name "Net-(J1-MODE)") (class "Default")
      (node (ref "J1") (pin "8") (pinfunction "MODE_8") (pintype "passive"))
      (node (ref "R1") (pin "1") (pinfunction "1_1") (pintype "passive"))
    )
    (net (code "81") (name "Net-(J1-RESET)") (class "Default")
      (node (ref "C2") (pin "2") (pinfunction "2_2") (pintype "passive"))
      (node (ref "J1") (pin "44") (pinfunction "RESET_44") (pintype "passive"))
      (node (ref "R2") (pin "1") (pinfunction "1_1") (pintype "passive"))
    )
    (net (code "82") (name "Net-(P3-VDD)") (class "Default")
      (node (ref "C8") (pin "2") (pinfunction "2_2") (pintype "passive"))
      (node (ref "C9") (pin "2") (pinfunction "2_2") (pintype "passive"))
      (node (ref "P3") (pin "2") (pinfunction "VDD_2") (pintype "passive"))
      (node (ref "R20") (pin "1") (pinfunction "1_1") (pintype "passive"))
    )
    (net (code "83") (name "Net-(U1-EN)") (class "Default")
      (node (ref "R18") (pin "2") (pinfunction "2_2") (pintype "passive"))
      (node (ref "U1") (pin "4") (pinfunction "EN_4") (pintype "passive"))
    )
    (net (code "84") (name "Net-(U2-EN)") (class "Default")
      (node (ref "R25") (pin "1") (pinfunction "1_1") (pintype "passive"))
      (node (ref "U2") (pin "4") (pinfunction "EN_4") (pintype "passive"))
    )
    (net (code "85") (name "Net-(U2-FB)") (class "Default")
      (node (ref "R26") (pin "1") (pinfunction "1_1") (pintype "passive"))
      (node (ref "R27") (pin "2") (pinfunction "2_2") (pintype "passive"))
      (node (ref "U2") (pin "3") (pinfunction "FB_3") (pintype "passive"))
    )
    (net (code "86") (name "Net-(U2-VIN)") (class "Default")
      (node (ref "B1") (pin "2") (pinfunction "2_2") (pintype "passive"))
      (node (ref "C14") (pin "2") (pinfunction "2_2") (pintype "passive"))
      (node (ref "C15") (pin "2") (pinfunction "2_2") (pintype "passive"))
      (node (ref "L2") (pin "1") (pinfunction "1_1") (pintype "passive"))
      (node (ref "R25") (pin "2") (pinfunction "2_2") (pintype "passive"))
      (node (ref "U2") (pin "6") (pinfunction "VIN_6") (pintype "passive"))
    )
    (net (code "87") (name "VCC-7") (class "Default")
      (node (ref "C11") (pin "2") (pinfunction "2_2") (pintype "passive"))
      (node (ref "D3") (pin "1") (pintype "passive"))
      (node (ref "J1") (pin "42") (pinfunction "VGL_42") (pintype "passive"))
      (node (ref "R21") (pin "2") (pinfunction "2_2") (pintype "passive"))
      (node (ref "R22") (pin "2") (pinfunction "2_2") (pintype "passive"))
    )
    (net (code "88") (name "VCC3.3") (class "Default")
      (node (ref "C18") (pin "2") (pinfunction "2_2") (pintype "passive"))
      (node (ref "C19") (pin "1") (pinfunction "1_1") (pintype "passive"))
      (node (ref "J1") (pin "7") (pinfunction "DVDD_7") (pintype "passive"))
      (node (ref "R1") (pin "2") (pinfunction "2_2") (pintype "passive"))
      (node (ref "R10") (pin "2") (pinfunction "2_2") (pintype "passive"))
      (node (ref "R12") (pin "2") (pinfunction "2_2") (pintype "passive"))
      (node (ref "R14") (pin "2") (pinfunction "2_2") (pintype "passive"))
      (node (ref "R16") (pin "1") (pinfunction "1_1") (pintype "passive"))
      (node (ref "R17") (pin "1") (pinfunction "1_1") (pintype "passive"))
      (node (ref "R2") (pin "2") (pinfunction "2_2") (pintype "passive"))
      (node (ref "R20") (pin "2") (pinfunction "2_2") (pintype "passive"))
      (node (ref "R3") (pin "2") (pinfunction "2_2") (pintype "passive"))
      (node (ref "R4") (pin "2") (pinfunction "2_2") (pintype "passive"))
      (node (ref "R7") (pin "2") (pinfunction "2_2") (pintype "passive"))
      (node (ref "VR1") (pin "2") (pinfunction "Vout_2") (pintype "passive"))
    )
    (net (code "89") (name "VCC5.0") (class "Default")
      (node (ref "B1") (pin "1") (pinfunction "1_1") (pintype "passive"))
      (node (ref "C1") (pin "1") (pinfunction "1_1") (pintype "passive"))
      (node (ref "C21") (pin "2") (pinfunction "2_2") (pintype "passive"))
      (node (ref "C22") (pin "2") (pinfunction "2_2") (pintype "passive"))
      (node (ref "C5") (pin "1") (pinfunction "1_1") (pintype "passive"))
      (node (ref "J2") (pin "1") (pinfunction "1_1") (pintype "passive"))
      (node (ref "J2") (pin "2") (pinfunction "2_2") (pintype "passive"))
      (node (ref "L1") (pin "1") (pinfunction "1_1") (pintype "passive"))
      (node (ref "U1") (pin "6") (pinfunction "VIN_6") (pintype "passive"))
      (node (ref "VR1") (pin "3") (pinfunction "Vin_3") (pintype "passive"))
    )
    (net (code "90") (name "VCC10.4") (class "Default")
      (node (ref "C24") (pin "2") (pinfunction "2_2") (pintype "passive"))
      (node (ref "C25") (pin "2") (pinfunction "2_2") (pintype "passive"))
      (node (ref "D5") (pin "1") (pintype "passive"))
      (node (ref "D7") (pin "2") (pinfunction "K_2") (pintype "passive"))
      (node (ref "J1") (pin "43") (pinfunction "AVDD_43") (pintype "passive"))
      (node (ref "R26") (pin "2") (pinfunction "2_2") (pintype "passive"))
      (node (ref "R8") (pin "2") (pinfunction "2_2") (pintype "passive"))
    )
    (net (code "91") (name "VCC16") (class "Default")
      (node (ref "C17") (pin "2") (pinfunction "2_2") (pintype "passive"))
      (node (ref "D6") (pin "2") (pintype "passive"))
      (node (ref "J1") (pin "41") (pinfunction "VGH_41") (pintype "passive"))
      (node (ref "R23") (pin "2") (pinfunction "2_2") (pintype "passive"))
      (node (ref "R24") (pin "2") (pinfunction "2_2") (pintype "passive"))
    )
    (net (code "92") (name "unconnected-(J1-NC-Pad45)") (class "Default")
      (node (ref "J1") (pin "45") (pinfunction "NC_45") (pintype "passive"))
    )
    (net (code "93") (name "unconnected-(J1-NC-Pad49)") (class "Default")
      (node (ref "J1") (pin "49") (pinfunction "NC_49") (pintype "passive"))
    )
    (net (code "94") (name "unconnected-(J1-NC-Pad50)") (class "Default")
      (node (ref "J1") (pin "50") (pinfunction "NC_50") (pintype "passive"))
    )
    (net (code "95") (name "unconnected-(J2-Pad37)") (class "Default")
      (node (ref "J2") (pin "37") (pinfunction "37_37") (pintype "passive"))
    )
    (net (code "96") (name "unconnected-(U2-NC-Pad5)") (class "Default")
      (node (ref "U2") (pin "5") (pinfunction "NC_5") (pintype "passive"))
    )
  )
)
